# 4th_MFB_LPF.net
KiCad netlist of a schematic drawn in EAGLE
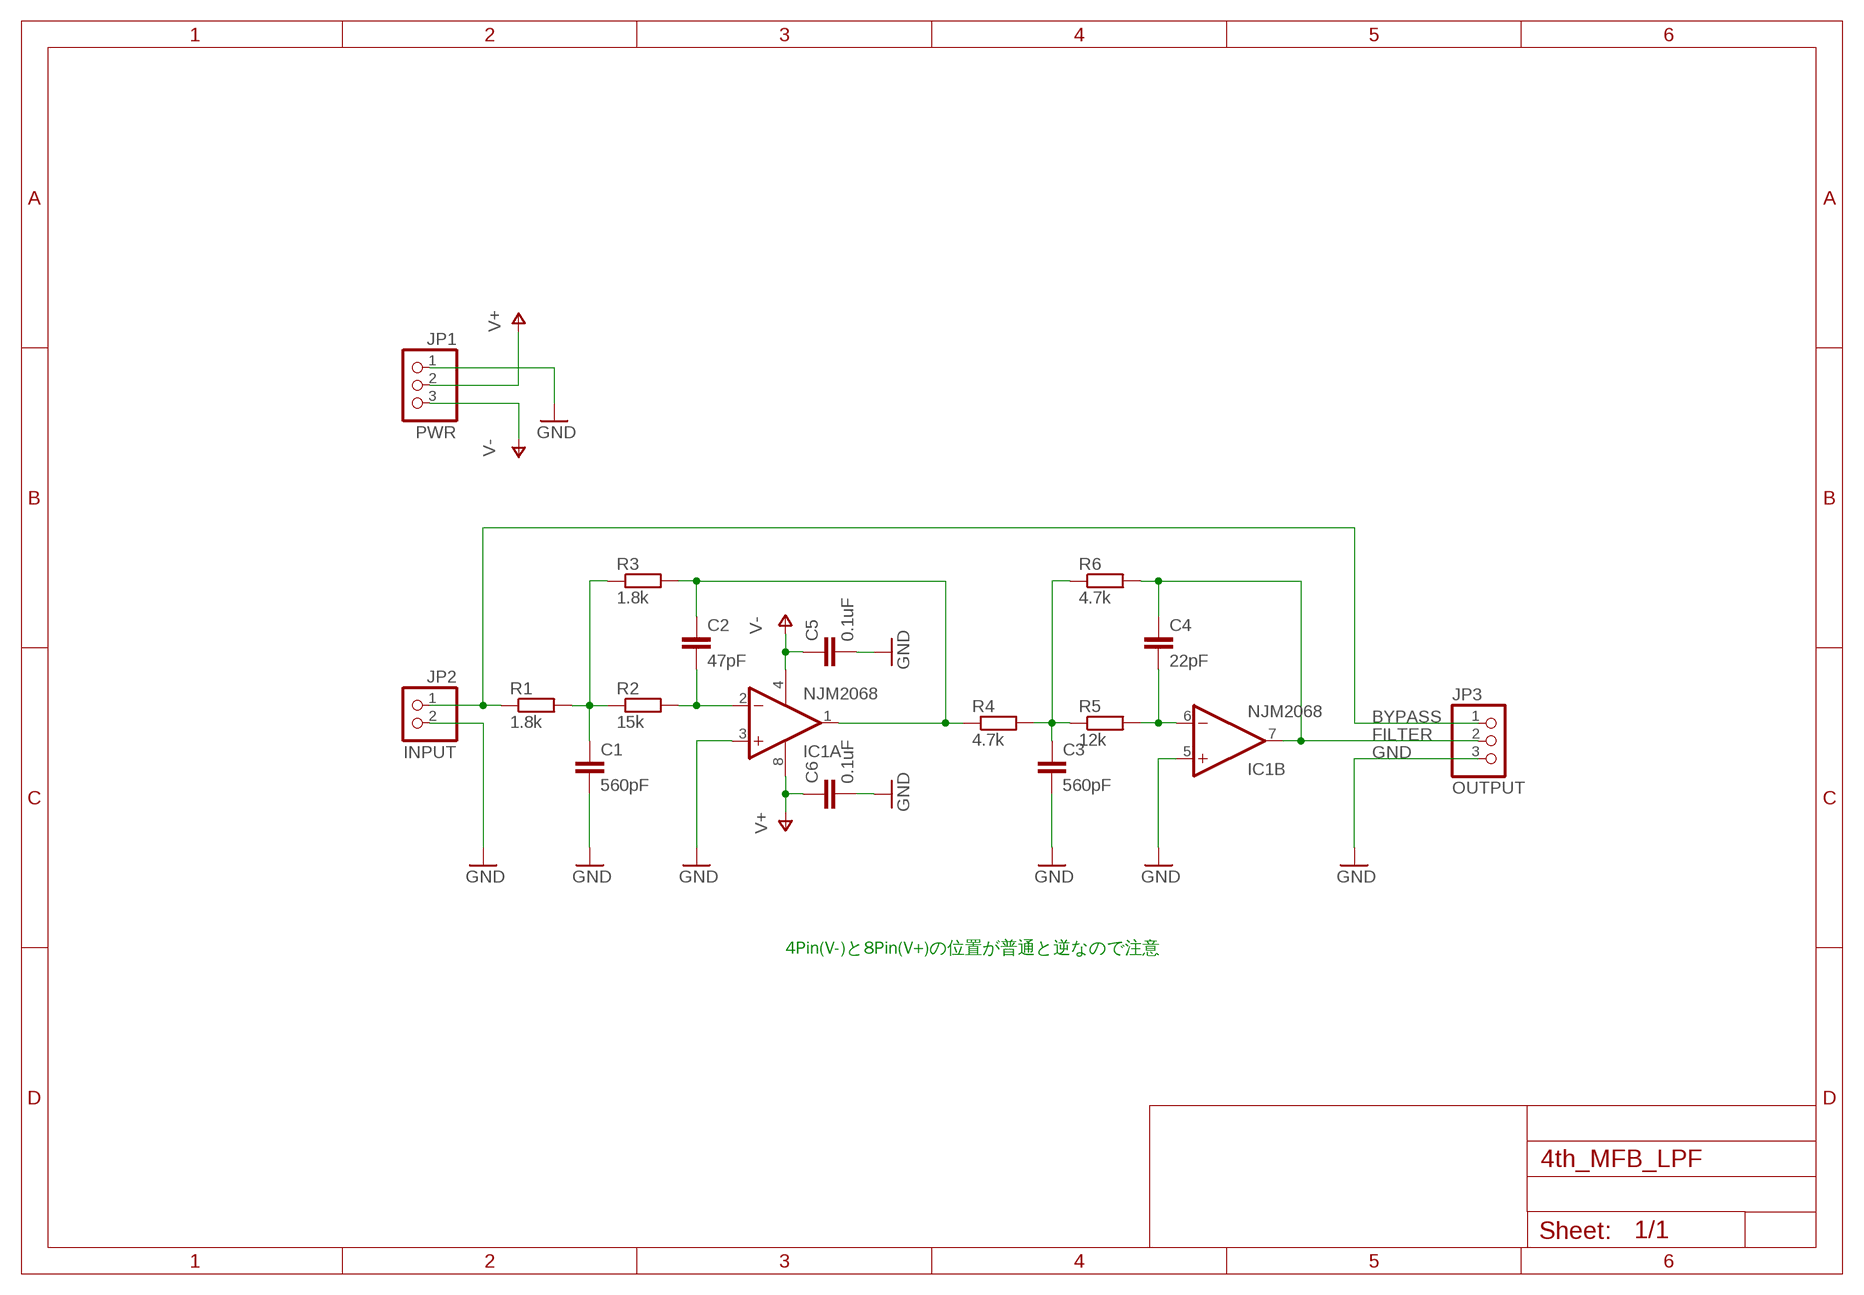
[diagram p0: schematic, sheet 1]

(export (version "E")
  (design (tool "Eeschema 10.0.6"))
  (components
    (comp (ref "C1")
      (value "560pF")
      (footprint "eagle-import:C050-030X075")
      (libsource (lib "eagle-import") (part "C-EU050-030X075"))
    )
    (comp (ref "C2")
      (value "47pF")
      (footprint "eagle-import:C050-030X075")
      (libsource (lib "eagle-import") (part "C-EU050-030X075"))
    )
    (comp (ref "C3")
      (value "560pF")
      (footprint "eagle-import:C050-030X075")
      (libsource (lib "eagle-import") (part "C-EU050-030X075"))
    )
    (comp (ref "C4")
      (value "22pF")
      (footprint "eagle-import:C050-030X075")
      (libsource (lib "eagle-import") (part "C-EU050-030X075"))
    )
    (comp (ref "C5")
      (value "0.1uF")
      (footprint "eagle-import:C025-024X044")
      (libsource (lib "eagle-import") (part "C-EU025-024X044"))
    )
    (comp (ref "C6")
      (value "0.1uF")
      (footprint "eagle-import:C050-024X044")
      (libsource (lib "eagle-import") (part "C-EU050-024X044"))
    )
    (comp (ref "IC1")
      (value "NJM2068")
      (footprint "eagle-import:DIL08")
      (libsource (lib "eagle-import") (part "LM358N"))
    )
    (comp (ref "JP1")
      (value "PWR")
      (footprint "eagle-import:1X03")
      (libsource (lib "eagle-import") (part "PINHD-1X3"))
    )
    (comp (ref "JP2")
      (value "INPUT")
      (footprint "eagle-import:1X02")
      (libsource (lib "eagle-import") (part "PINHD-1X2"))
    )
    (comp (ref "JP3")
      (value "OUTPUT")
      (footprint "eagle-import:1X03")
      (libsource (lib "eagle-import") (part "PINHD-1X3"))
    )
    (comp (ref "R1")
      (value "1.8k")
      (footprint "eagle-import:0207_7")
      (libsource (lib "eagle-import") (part "R-EU_0207/7"))
    )
    (comp (ref "R2")
      (value "15k")
      (footprint "eagle-import:0207_7")
      (libsource (lib "eagle-import") (part "R-EU_0207/7"))
    )
    (comp (ref "R3")
      (value "1.8k")
      (footprint "eagle-import:0207_7")
      (libsource (lib "eagle-import") (part "R-EU_0207/7"))
    )
    (comp (ref "R4")
      (value "4.7k")
      (footprint "eagle-import:0207_7")
      (libsource (lib "eagle-import") (part "R-EU_0207/7"))
    )
    (comp (ref "R5")
      (value "12k")
      (footprint "eagle-import:0207_7")
      (libsource (lib "eagle-import") (part "R-EU_0207/7"))
    )
    (comp (ref "R6")
      (value "4.7k")
      (footprint "eagle-import:0207_7")
      (libsource (lib "eagle-import") (part "R-EU_0207/7"))
    )
  )
  (nets
    (net (code "1") (name "/BYPASS") (class "Default")
      (node (ref "JP2") (pin "1") (pinfunction "1_1") (pintype "passive"))
      (node (ref "JP3") (pin "1") (pinfunction "1_1") (pintype "passive"))
      (node (ref "R1") (pin "1") (pinfunction "1_1") (pintype "passive"))
    )
    (net (code "2") (name "/FILTER") (class "Default")
      (node (ref "C4") (pin "1") (pinfunction "1_1") (pintype "passive"))
      (node (ref "IC1") (pin "7") (pinfunction "OUT_7") (pintype "output"))
      (node (ref "JP3") (pin "2") (pinfunction "2_2") (pintype "passive"))
      (node (ref "R6") (pin "2") (pinfunction "2_2") (pintype "passive"))
    )
    (net (code "3") (name "GND") (class "Default")
      (node (ref "C1") (pin "2") (pinfunction "2_2") (pintype "passive"))
      (node (ref "C3") (pin "2") (pinfunction "2_2") (pintype "passive"))
      (node (ref "C5") (pin "2") (pinfunction "2_2") (pintype "passive"))
      (node (ref "C6") (pin "2") (pinfunction "2_2") (pintype "passive"))
      (node (ref "IC1") (pin "3") (pinfunction "+IN_3") (pintype "input"))
      (node (ref "IC1") (pin "5") (pinfunction "+IN_5") (pintype "input"))
      (node (ref "JP1") (pin "1") (pinfunction "1_1") (pintype "passive"))
      (node (ref "JP2") (pin "2") (pinfunction "2_2") (pintype "passive"))
      (node (ref "JP3") (pin "3") (pinfunction "3_3") (pintype "passive"))
    )
    (net (code "4") (name "Net-(C1-Pad1)") (class "Default")
      (node (ref "C1") (pin "1") (pinfunction "1_1") (pintype "passive"))
      (node (ref "R1") (pin "2") (pinfunction "2_2") (pintype "passive"))
      (node (ref "R2") (pin "1") (pinfunction "1_1") (pintype "passive"))
      (node (ref "R3") (pin "1") (pinfunction "1_1") (pintype "passive"))
    )
    (net (code "5") (name "Net-(C3-Pad1)") (class "Default")
      (node (ref "C3") (pin "1") (pinfunction "1_1") (pintype "passive"))
      (node (ref "R4") (pin "2") (pinfunction "2_2") (pintype "passive"))
      (node (ref "R5") (pin "1") (pinfunction "1_1") (pintype "passive"))
      (node (ref "R6") (pin "1") (pinfunction "1_1") (pintype "passive"))
    )
    (net (code "6") (name "Net-(IC1A--IN)") (class "Default")
      (node (ref "C2") (pin "2") (pinfunction "2_2") (pintype "passive"))
      (node (ref "IC1") (pin "2") (pinfunction "-IN_2") (pintype "input"))
      (node (ref "R2") (pin "2") (pinfunction "2_2") (pintype "passive"))
    )
    (net (code "7") (name "Net-(IC1A-OUT)") (class "Default")
      (node (ref "C2") (pin "1") (pinfunction "1_1") (pintype "passive"))
      (node (ref "IC1") (pin "1") (pinfunction "OUT_1") (pintype "output"))
      (node (ref "R3") (pin "2") (pinfunction "2_2") (pintype "passive"))
      (node (ref "R4") (pin "1") (pinfunction "1_1") (pintype "passive"))
    )
    (net (code "8") (name "Net-(IC1B--IN)") (class "Default")
      (node (ref "C4") (pin "2") (pinfunction "2_2") (pintype "passive"))
      (node (ref "IC1") (pin "6") (pinfunction "-IN_6") (pintype "input"))
      (node (ref "R5") (pin "2") (pinfunction "2_2") (pintype "passive"))
    )
    (net (code "9") (name "V+") (class "Default")
      (node (ref "C6") (pin "1") (pinfunction "1_1") (pintype "passive"))
      (node (ref "IC1") (pin "8") (pinfunction "V+_8") (pintype "power_in"))
      (node (ref "JP1") (pin "2") (pinfunction "2_2") (pintype "passive"))
    )
    (net (code "10") (name "V-") (class "Default")
      (node (ref "C5") (pin "1") (pinfunction "1_1") (pintype "passive"))
      (node (ref "IC1") (pin "4") (pinfunction "V-_4") (pintype "power_in"))
      (node (ref "JP1") (pin "3") (pinfunction "3_3") (pintype "passive"))
    )
  )
)
